# BT_PCM5102A_OPA227.net
KiCad netlist of a schematic drawn in EAGLE
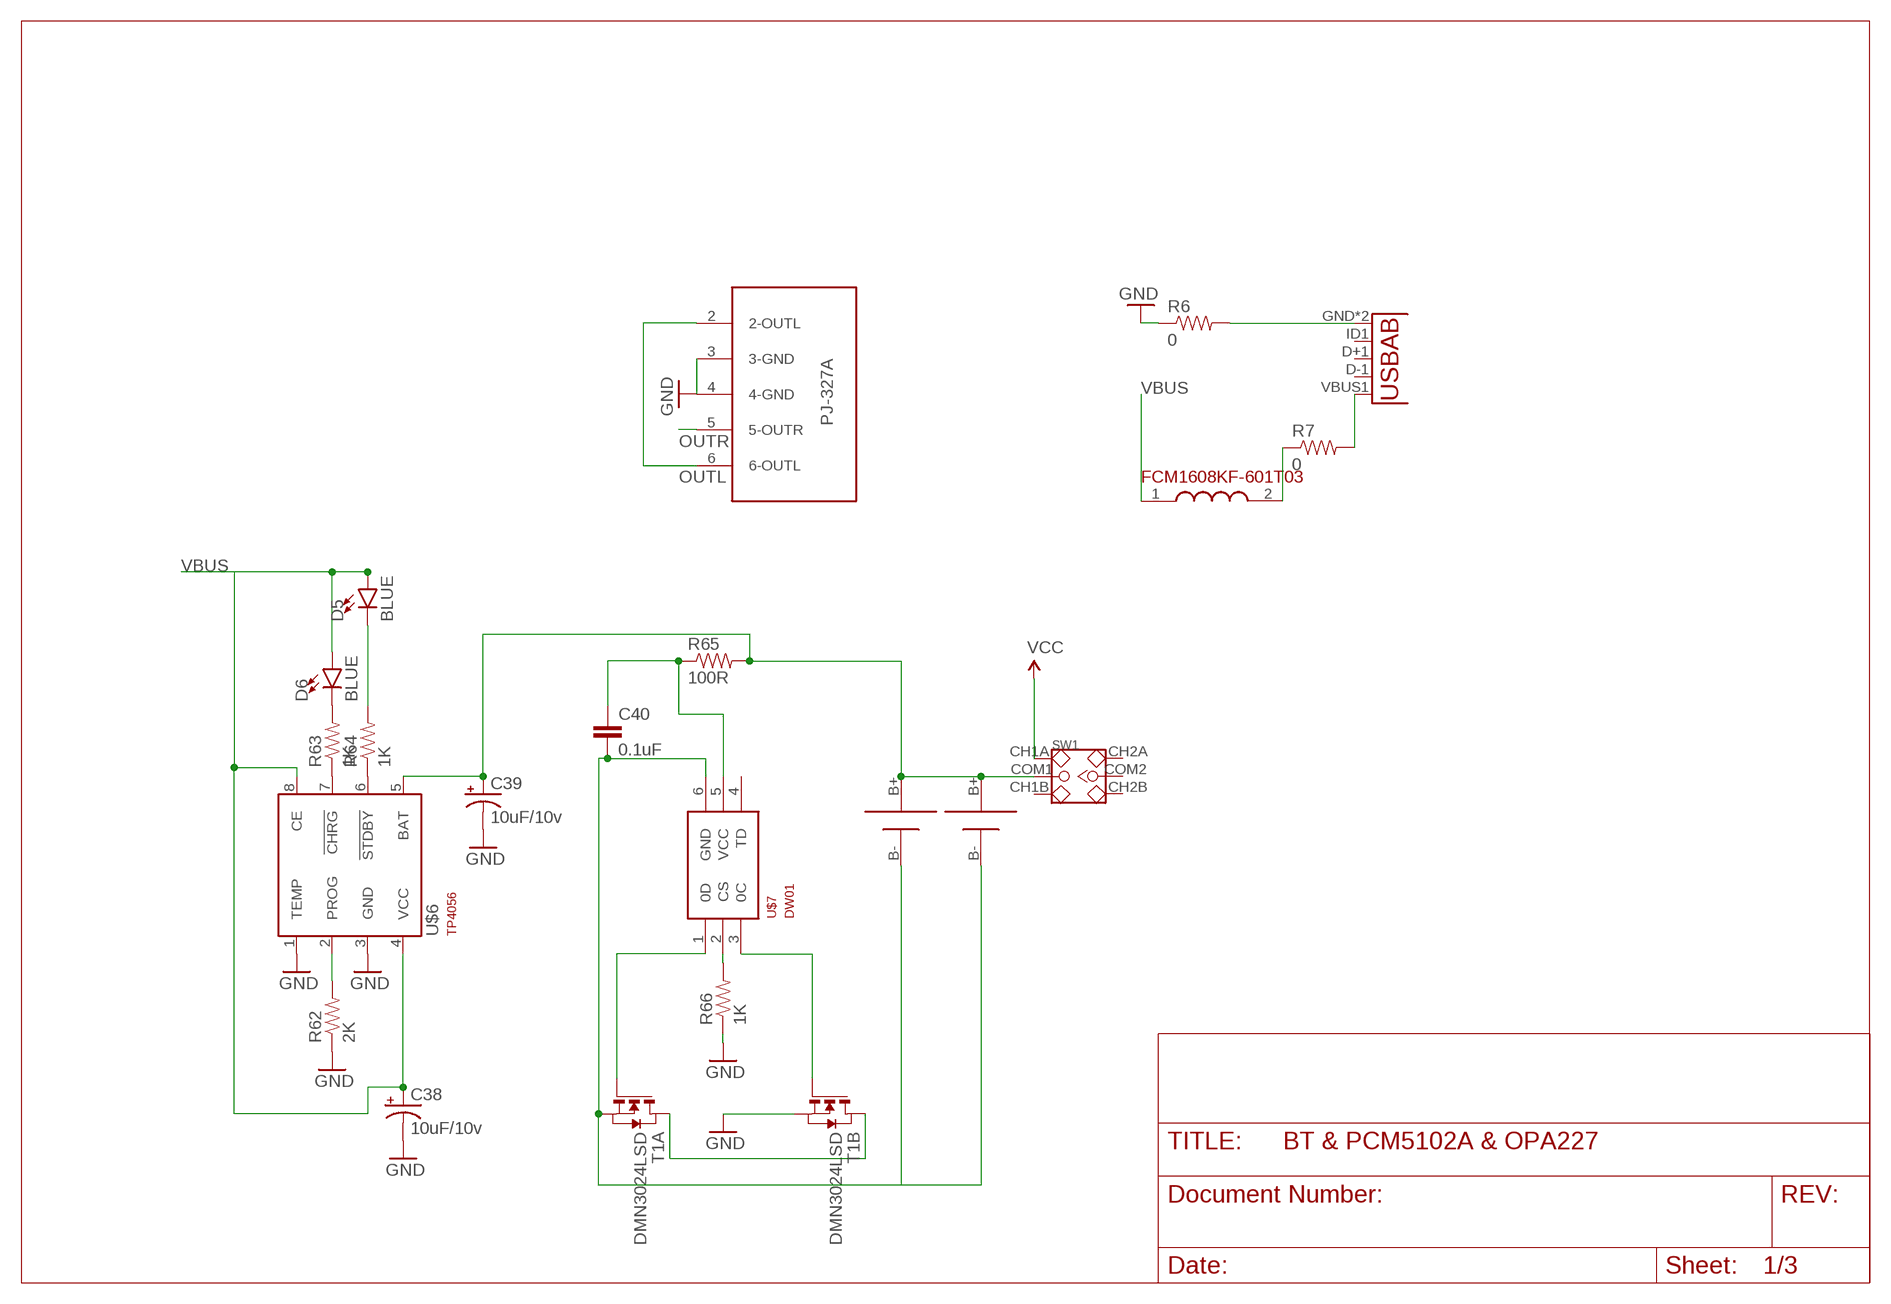
[diagram p0: schematic, sheet 1]
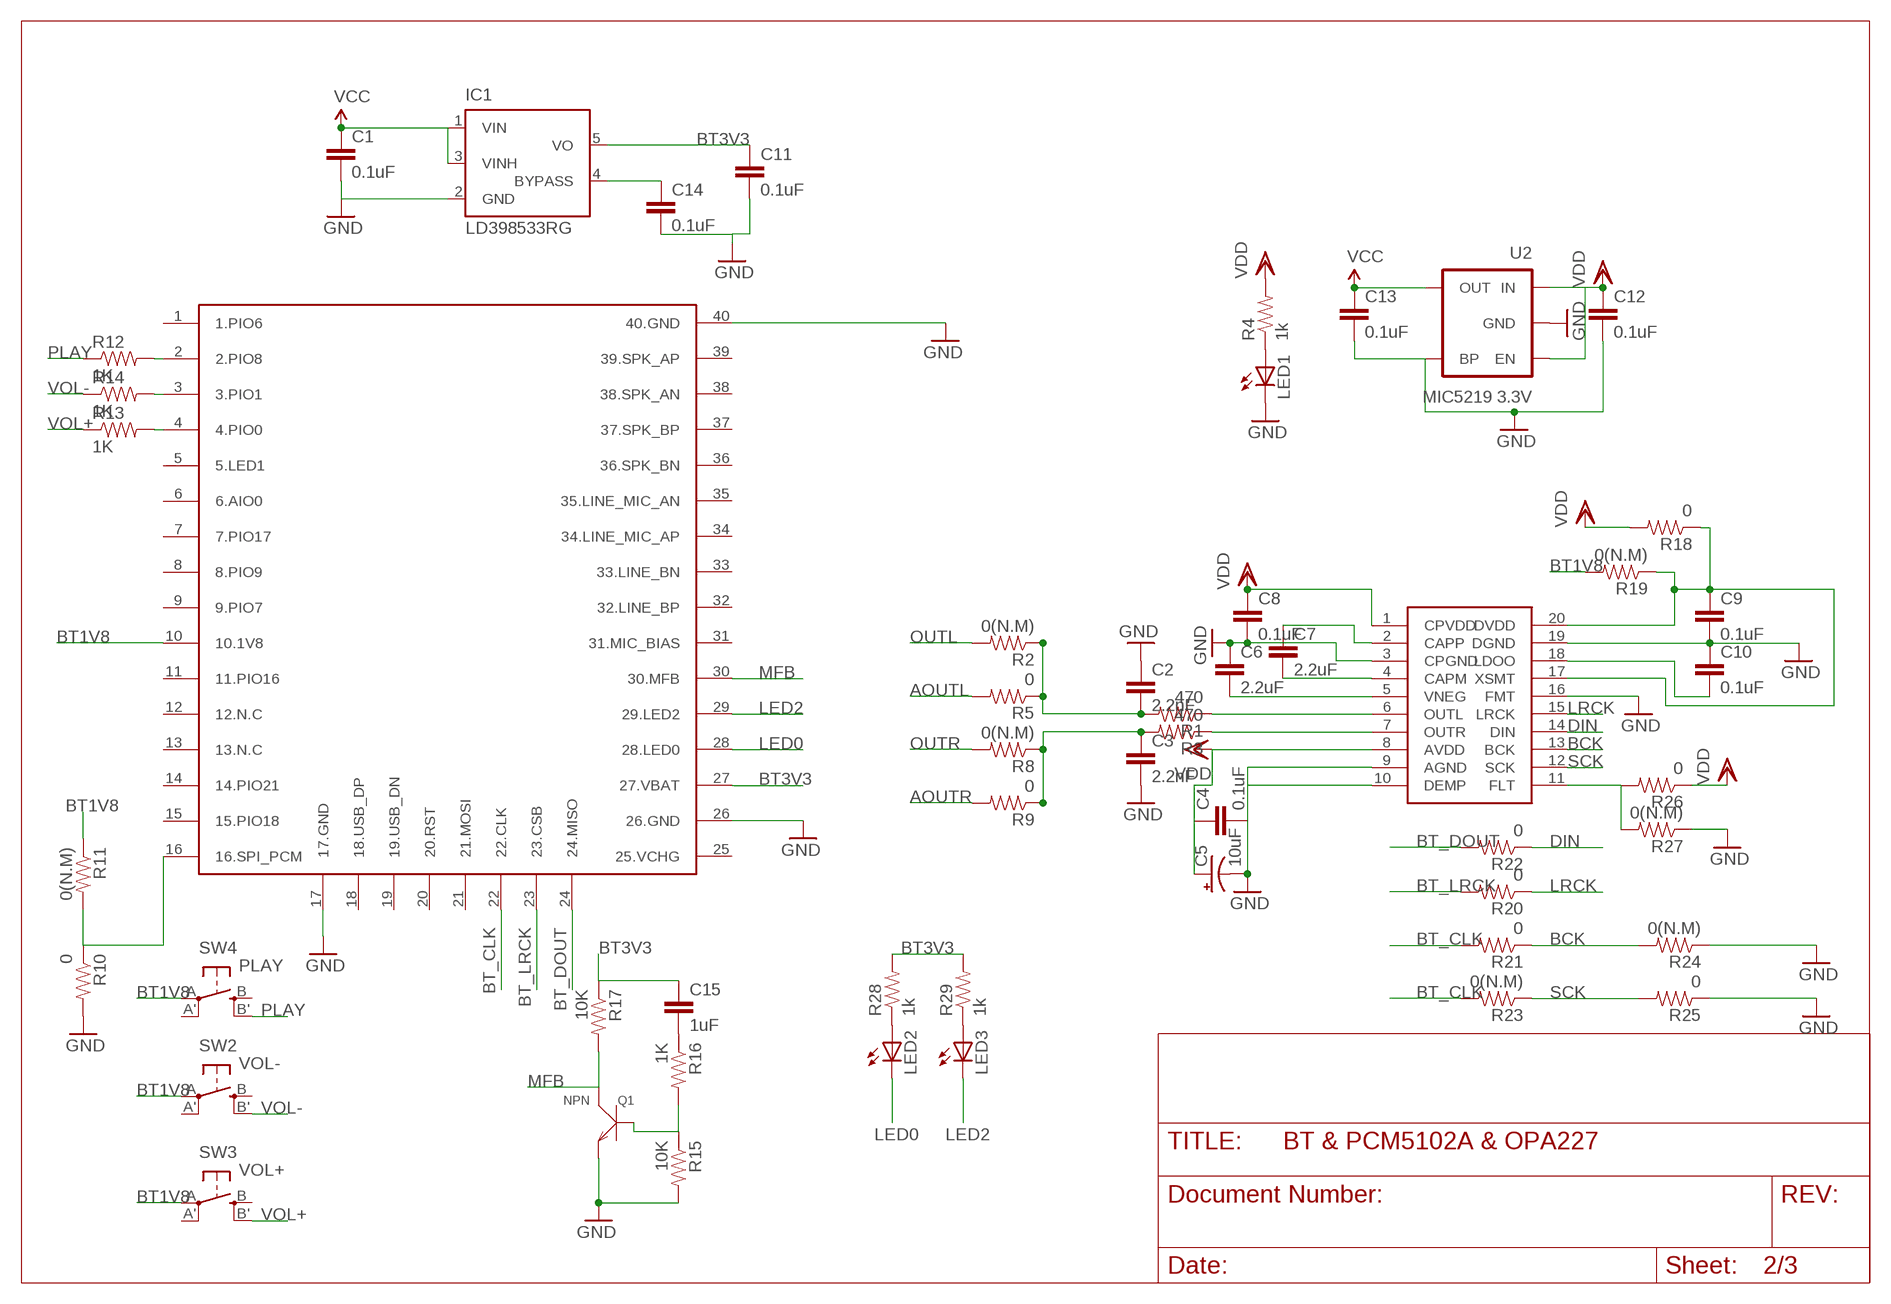
[diagram p1: schematic, sheet 2]
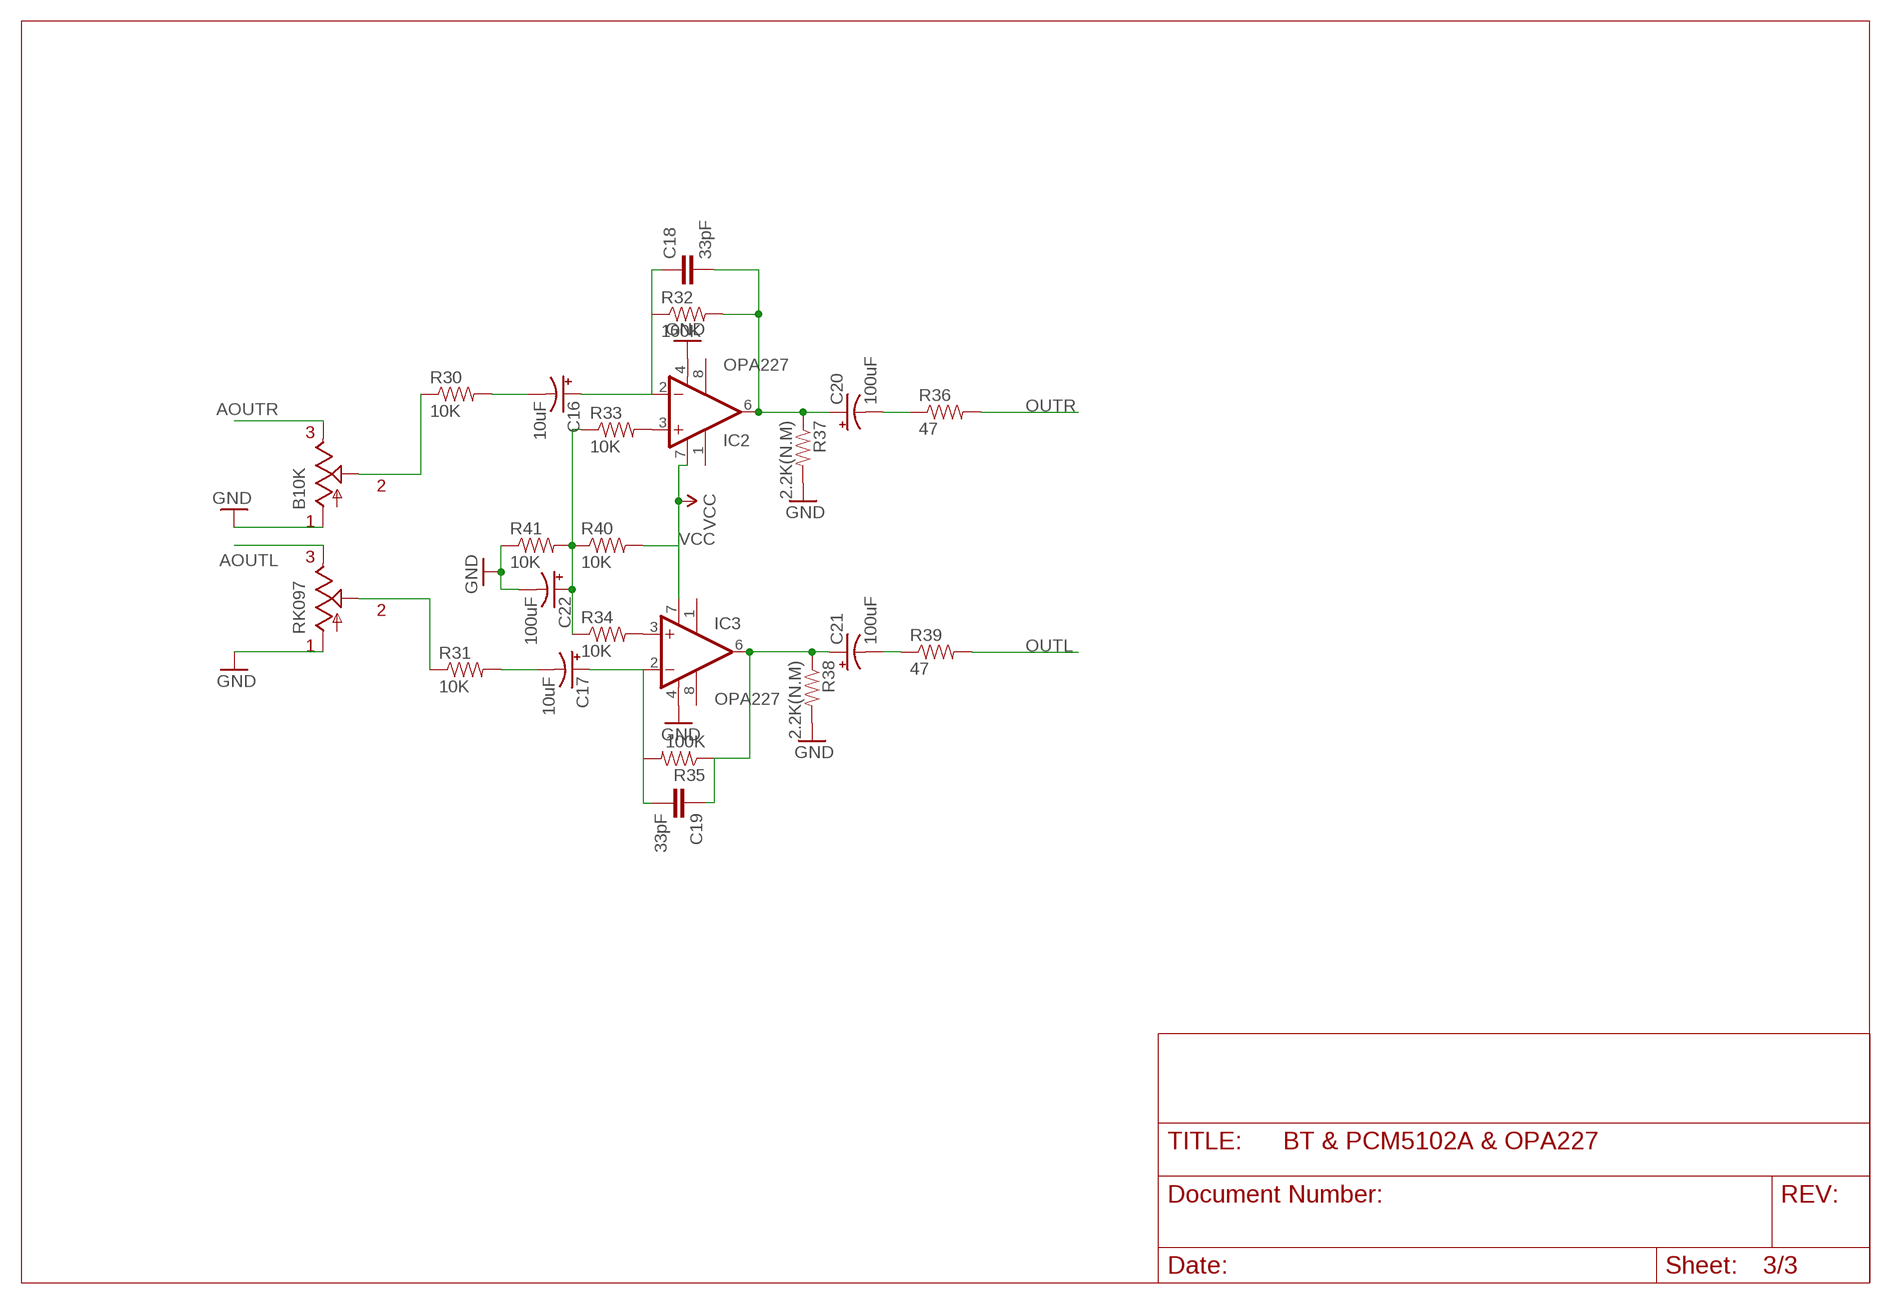
[diagram p2: schematic, sheet 3]

(export (version "E")
  (design (tool "Eeschema 10.0.6"))
  (components
    (comp (ref "C1")
      (value "0.1uF")
      (footprint "eagle-import:1206")
      (libsource (lib "eagle-import") (part "2.2UF-CERCAP-10009"))
    )
    (comp (ref "C2")
      (value "2.2nF")
      (footprint "eagle-import:C5B2.5")
      (libsource (lib "eagle-import") (part "C5/2.5"))
    )
    (comp (ref "C3")
      (value "2.2nF")
      (footprint "eagle-import:C5B2.5")
      (libsource (lib "eagle-import") (part "C5/2.5"))
    )
    (comp (ref "C4")
      (value "0.1uF")
      (footprint "eagle-import:1206")
      (libsource (lib "eagle-import") (part "2.2UF-CERCAP-10009"))
    )
    (comp (ref "C5")
      (value "10uF")
      (footprint "eagle-import:NIPPON_F80")
      (libsource (lib "eagle-import") (part "CAP_POLF80"))
    )
    (comp (ref "C6")
      (value "2.2uF")
      (footprint "eagle-import:1206")
      (libsource (lib "eagle-import") (part "2.2UF-CERCAP-10009"))
    )
    (comp (ref "C7")
      (value "2.2uF")
      (footprint "eagle-import:1206")
      (libsource (lib "eagle-import") (part "2.2UF-CERCAP-10009"))
    )
    (comp (ref "C8")
      (value "0.1uF")
      (footprint "eagle-import:1206")
      (libsource (lib "eagle-import") (part "2.2UF-CERCAP-10009"))
    )
    (comp (ref "C9")
      (value "0.1uF")
      (footprint "eagle-import:1206")
      (libsource (lib "eagle-import") (part "2.2UF-CERCAP-10009"))
    )
    (comp (ref "C10")
      (value "0.1uF")
      (footprint "eagle-import:1206")
      (libsource (lib "eagle-import") (part "2.2UF-CERCAP-10009"))
    )
    (comp (ref "C11")
      (value "0.1uF")
      (footprint "eagle-import:1206")
      (libsource (lib "eagle-import") (part "2.2UF-CERCAP-10009"))
    )
    (comp (ref "C12")
      (value "0.1uF")
      (footprint "eagle-import:1206")
      (libsource (lib "eagle-import") (part "2.2UF-CERCAP-10009"))
    )
    (comp (ref "C13")
      (value "0.1uF")
      (footprint "eagle-import:1206")
      (libsource (lib "eagle-import") (part "2.2UF-CERCAP-10009"))
    )
    (comp (ref "C14")
      (value "0.1uF")
      (footprint "eagle-import:1206")
      (libsource (lib "eagle-import") (part "2.2UF-CERCAP-10009"))
    )
    (comp (ref "C15")
      (value "1uF")
      (footprint "eagle-import:C5B2.5")
      (libsource (lib "eagle-import") (part "C5/2.5"))
    )
    (comp (ref "IC1")
      (value "LD398533RG")
      (footprint "eagle-import:TSOT23-5L")
      (libsource (lib "eagle-import") (part "LD3985G33R"))
    )
    (comp (ref "LED1")
      (value "LEDCHIP-LED0805")
      (footprint "eagle-import:CHIP-LED0805")
      (libsource (lib "eagle-import") (part "LEDCHIP-LED0805"))
    )
    (comp (ref "LED2")
      (value "LEDCHIP-LED0805")
      (footprint "eagle-import:CHIP-LED0805")
      (libsource (lib "eagle-import") (part "LEDCHIP-LED0805"))
    )
    (comp (ref "LED3")
      (value "LEDCHIP-LED0805")
      (footprint "eagle-import:CHIP-LED0805")
      (libsource (lib "eagle-import") (part "LEDCHIP-LED0805"))
    )
    (comp (ref "Q1")
      (value "NPN")
      (footprint "eagle-import:SOT-23")
      (libsource (lib "eagle-import") (part "TRANSISTOR-NPN"))
    )
    (comp (ref "R1")
      (value "470")
      (footprint "eagle-import:1206")
      (libsource (lib "eagle-import") (part "RESISTOR1206"))
    )
    (comp (ref "R2")
      (value "0(N.M)")
      (footprint "eagle-import:1206")
      (libsource (lib "eagle-import") (part "RESISTOR1206"))
    )
    (comp (ref "R3")
      (value "470")
      (footprint "eagle-import:1206")
      (libsource (lib "eagle-import") (part "RESISTOR1206"))
    )
    (comp (ref "R4")
      (value "1k")
      (footprint "eagle-import:1206")
      (libsource (lib "eagle-import") (part "RESISTOR1206"))
    )
    (comp (ref "R5")
      (value "0")
      (footprint "eagle-import:1206")
      (libsource (lib "eagle-import") (part "RESISTOR1206"))
    )
    (comp (ref "R8")
      (value "0(N.M)")
      (footprint "eagle-import:1206")
      (libsource (lib "eagle-import") (part "RESISTOR1206"))
    )
    (comp (ref "R9")
      (value "0")
      (footprint "eagle-import:1206")
      (libsource (lib "eagle-import") (part "RESISTOR1206"))
    )
    (comp (ref "R10")
      (value "0")
      (footprint "eagle-import:1206")
      (libsource (lib "eagle-import") (part "RESISTOR1206"))
    )
    (comp (ref "R11")
      (value "0(N.M)")
      (footprint "eagle-import:1206")
      (libsource (lib "eagle-import") (part "RESISTOR1206"))
    )
    (comp (ref "R12")
      (value "1K")
      (footprint "eagle-import:1206")
      (libsource (lib "eagle-import") (part "RESISTOR1206"))
    )
    (comp (ref "R13")
      (value "1K")
      (footprint "eagle-import:1206")
      (libsource (lib "eagle-import") (part "RESISTOR1206"))
    )
    (comp (ref "R14")
      (value "1K")
      (footprint "eagle-import:1206")
      (libsource (lib "eagle-import") (part "RESISTOR1206"))
    )
    (comp (ref "R15")
      (value "10K")
      (footprint "eagle-import:1206")
      (libsource (lib "eagle-import") (part "RESISTOR1206"))
    )
    (comp (ref "R16")
      (value "1K")
      (footprint "eagle-import:1206")
      (libsource (lib "eagle-import") (part "RESISTOR1206"))
    )
    (comp (ref "R17")
      (value "10K")
      (footprint "eagle-import:1206")
      (libsource (lib "eagle-import") (part "RESISTOR1206"))
    )
    (comp (ref "R18")
      (value "0")
      (footprint "eagle-import:1206")
      (libsource (lib "eagle-import") (part "RESISTOR1206"))
    )
    (comp (ref "R19")
      (value "0(N.M)")
      (footprint "eagle-import:1206")
      (libsource (lib "eagle-import") (part "RESISTOR1206"))
    )
    (comp (ref "R20")
      (value "0")
      (footprint "eagle-import:1206")
      (libsource (lib "eagle-import") (part "RESISTOR1206"))
    )
    (comp (ref "R21")
      (value "0")
      (footprint "eagle-import:1206")
      (libsource (lib "eagle-import") (part "RESISTOR1206"))
    )
    (comp (ref "R22")
      (value "0")
      (footprint "eagle-import:1206")
      (libsource (lib "eagle-import") (part "RESISTOR1206"))
    )
    (comp (ref "R23")
      (value "0(N.M)")
      (footprint "eagle-import:1206")
      (libsource (lib "eagle-import") (part "RESISTOR1206"))
    )
    (comp (ref "R24")
      (value "0(N.M)")
      (footprint "eagle-import:1206")
      (libsource (lib "eagle-import") (part "RESISTOR1206"))
    )
    (comp (ref "R25")
      (value "0")
      (footprint "eagle-import:1206")
      (libsource (lib "eagle-import") (part "RESISTOR1206"))
    )
    (comp (ref "R26")
      (value "0")
      (footprint "eagle-import:1206")
      (libsource (lib "eagle-import") (part "RESISTOR1206"))
    )
    (comp (ref "R27")
      (value "0(N.M)")
      (footprint "eagle-import:1206")
      (libsource (lib "eagle-import") (part "RESISTOR1206"))
    )
    (comp (ref "R28")
      (value "1k")
      (footprint "eagle-import:1206")
      (libsource (lib "eagle-import") (part "RESISTOR1206"))
    )
    (comp (ref "R29")
      (value "1k")
      (footprint "eagle-import:1206")
      (libsource (lib "eagle-import") (part "RESISTOR1206"))
    )
    (comp (ref "SW2")
      (value "VOL-")
      (footprint "eagle-import:EVQ-Q2")
      (libsource (lib "eagle-import") (part "SPST_TACT-EVQQ2"))
    )
    (comp (ref "SW3")
      (value "VOL+")
      (footprint "eagle-import:EVQ-Q2")
      (libsource (lib "eagle-import") (part "SPST_TACT-EVQQ2"))
    )
    (comp (ref "SW4")
      (value "PLAY")
      (footprint "eagle-import:EVQ-Q2")
      (libsource (lib "eagle-import") (part "SPST_TACT-EVQQ2"))
    )
    (comp (ref "U$1")
      (value "PCM5102")
      (footprint "eagle-import:TSSOP20")
      (libsource (lib "eagle-import") (part "PCM5102"))
    )
    (comp (ref "U$3")
      (value "BTM625")
      (footprint "eagle-import:BTM625")
      (libsource (lib "eagle-import") (part "BTM625"))
    )
    (comp (ref "U2")
      (value "MIC5219 3.3V")
      (footprint "eagle-import:SOT23-5")
      (libsource (lib "eagle-import") (part "V_REG_MIC52193.3V"))
    )
    (comp (ref "C16")
      (value "10uF")
      (footprint "eagle-import:CPOL-RADIAL-2.5MM-5MM-KIT")
      (libsource (lib "eagle-import") (part "10UF-POLAR-RADIAL-2.5MM-KIT-25V-20%"))
    )
    (comp (ref "C17")
      (value "10uF")
      (footprint "eagle-import:CPOL-RADIAL-2.5MM-5MM-KIT")
      (libsource (lib "eagle-import") (part "10UF-POLAR-RADIAL-2.5MM-KIT-25V-20%"))
    )
    (comp (ref "C18")
      (value "33pF")
      (footprint "eagle-import:0603")
      (libsource (lib "eagle-import") (part "22PF-0603-50V-5%"))
    )
    (comp (ref "C19")
      (value "33pF")
      (footprint "eagle-import:0603")
      (libsource (lib "eagle-import") (part "22PF-0603-50V-5%"))
    )
    (comp (ref "C20")
      (value "100uF")
      (footprint "eagle-import:CPOL-RADIAL-2.5MM-5MM-KIT")
      (libsource (lib "eagle-import") (part "10UF-POLAR-RADIAL-2.5MM-KIT-25V-20%"))
    )
    (comp (ref "C21")
      (value "100uF")
      (footprint "eagle-import:CPOL-RADIAL-2.5MM-5MM-KIT")
      (libsource (lib "eagle-import") (part "10UF-POLAR-RADIAL-2.5MM-KIT-25V-20%"))
    )
    (comp (ref "C22")
      (value "100uF")
      (footprint "eagle-import:CPOL-RADIAL-2.5MM-5MM-KIT")
      (libsource (lib "eagle-import") (part "10UF-POLAR-RADIAL-2.5MM-KIT-25V-20%"))
    )
    (comp (ref "IC2")
      (value "OPA227")
      (footprint "eagle-import:SO08")
      (libsource (lib "eagle-import") (part "OPA22D"))
    )
    (comp (ref "IC3")
      (value "OPA227")
      (footprint "eagle-import:SO08")
      (libsource (lib "eagle-import") (part "OPA22D"))
    )
    (comp (ref "R30")
      (value "10K")
      (footprint "eagle-import:1206")
      (libsource (lib "eagle-import") (part "RESISTOR1206"))
    )
    (comp (ref "R31")
      (value "10K")
      (footprint "eagle-import:1206")
      (libsource (lib "eagle-import") (part "RESISTOR1206"))
    )
    (comp (ref "R32")
      (value "100K")
      (footprint "eagle-import:1206")
      (libsource (lib "eagle-import") (part "RESISTOR1206"))
    )
    (comp (ref "R33")
      (value "10K")
      (footprint "eagle-import:1206")
      (libsource (lib "eagle-import") (part "RESISTOR1206"))
    )
    (comp (ref "R34")
      (value "10K")
      (footprint "eagle-import:1206")
      (libsource (lib "eagle-import") (part "RESISTOR1206"))
    )
    (comp (ref "R35")
      (value "100K")
      (footprint "eagle-import:1206")
      (libsource (lib "eagle-import") (part "RESISTOR1206"))
    )
    (comp (ref "R36")
      (value "47")
      (footprint "eagle-import:1206")
      (libsource (lib "eagle-import") (part "RESISTOR1206"))
    )
    (comp (ref "R37")
      (value "2.2K(N.M)")
      (footprint "eagle-import:1206")
      (libsource (lib "eagle-import") (part "RESISTOR1206"))
    )
    (comp (ref "R38")
      (value "2.2K(N.M)")
      (footprint "eagle-import:1206")
      (libsource (lib "eagle-import") (part "RESISTOR1206"))
    )
    (comp (ref "R39")
      (value "47")
      (footprint "eagle-import:1206")
      (libsource (lib "eagle-import") (part "RESISTOR1206"))
    )
    (comp (ref "R40")
      (value "10K")
      (footprint "eagle-import:1206")
      (libsource (lib "eagle-import") (part "RESISTOR1206"))
    )
    (comp (ref "R41")
      (value "10K")
      (footprint "eagle-import:1206")
      (libsource (lib "eagle-import") (part "RESISTOR1206"))
    )
    (comp (ref "RK097")
      (value "B10K")
      (footprint "eagle-import:RK097-DUAL-ELEMENT")
      (libsource (lib "eagle-import") (part "RK097-DUAL-ELEMENT"))
    )
    (comp (ref "C38")
      (value "10uF/10v")
      (footprint "eagle-import:EIA3216-KIT")
      (libsource (lib "eagle-import") (part "CAP_POL1206-KIT"))
    )
    (comp (ref "C39")
      (value "10uF/10v")
      (footprint "eagle-import:EIA3216-KIT")
      (libsource (lib "eagle-import") (part "CAP_POL1206-KIT"))
    )
    (comp (ref "C40")
      (value "0.1uF")
      (footprint "eagle-import:0603-CAP")
      (libsource (lib "eagle-import") (part "0.1UF-100V-10%(0603)"))
    )
    (comp (ref "D5")
      (value "BLUE")
      (footprint "eagle-import:LED-0603")
      (libsource (lib "eagle-import") (part "LED-BLUE0603"))
    )
    (comp (ref "D6")
      (value "BLUE")
      (footprint "eagle-import:LED-0603")
      (libsource (lib "eagle-import") (part "LED-BLUE0603"))
    )
    (comp (ref "R6")
      (value "0")
      (footprint "eagle-import:0805")
      (libsource (lib "eagle-import") (part "RESISTOR0805-RES"))
    )
    (comp (ref "R7")
      (value "0")
      (footprint "eagle-import:0805")
      (libsource (lib "eagle-import") (part "RESISTOR0805-RES"))
    )
    (comp (ref "R62")
      (value "2K")
      (footprint "eagle-import:0603-RES")
      (libsource (lib "eagle-import") (part "1KOHM1/10W1%(0603)"))
    )
    (comp (ref "R63")
      (value "1K")
      (footprint "eagle-import:0603-RES")
      (libsource (lib "eagle-import") (part "1KOHM1/10W1%(0603)"))
    )
    (comp (ref "R64")
      (value "1K")
      (footprint "eagle-import:0603-RES")
      (libsource (lib "eagle-import") (part "1KOHM1/10W1%(0603)"))
    )
    (comp (ref "R65")
      (value "100R")
      (footprint "eagle-import:0603-RES")
      (libsource (lib "eagle-import") (part "1KOHM1/10W1%(0603)"))
    )
    (comp (ref "R66")
      (value "1K")
      (footprint "eagle-import:0603-RES")
      (libsource (lib "eagle-import") (part "1KOHM1/10W1%(0603)"))
    )
    (comp (ref "SW1")
      (value "SMD-TOGGLE-SWITCH-2CH(2X3P-7X3.5MM)")
      (footprint "eagle-import:SW6-2.54-SMD-7.0X3.5X1.5MM")
      (libsource (lib "eagle-import") (part "SMD-TOGGLE-SWITCH-2CH(2X3P-7X3.5MM)"))
    )
    (comp (ref "T1")
      (value "DMN3024LSD")
      (footprint "eagle-import:TSSOP-8")
      (libsource (lib "eagle-import") (part "DMN3024LSD"))
    )
    (comp (ref "U$2")
      (value "PJ-327A")
      (footprint "eagle-import:PJ-327A")
      (libsource (lib "eagle-import") (part "PJ-327A"))
    )
    (comp (ref "U$4")
      (value "FCM1608KF-601T03")
      (footprint "eagle-import:FCM1608KF-601T03")
      (libsource (lib "eagle-import") (part "FCM1608KF-601T03"))
    )
    (comp (ref "U$5")
      (value "18650SMD")
      (footprint "eagle-import:18650SMD")
      (libsource (lib "eagle-import") (part "18650SMD"))
    )
    (comp (ref "U$6")
      (value "TP4056")
      (footprint "eagle-import:SOT23-8")
      (libsource (lib "eagle-import") (part "TP4056"))
    )
    (comp (ref "U$7")
      (value "DW01")
      (footprint "eagle-import:SOT23-6")
      (libsource (lib "eagle-import") (part "DW01"))
    )
    (comp (ref "U$8")
      (value "18650SMD")
      (footprint "eagle-import:18650SMD")
      (libsource (lib "eagle-import") (part "18650SMD"))
    )
    (comp (ref "U1")
      (value "USB\"\"")
      (footprint "eagle-import:USB-MICRO-SMD")
      (libsource (lib "eagle-import") (part "USB{dblquote}{dblquote}"))
    )
  )
  (nets
    (net (code "1") (name "AOUTL") (class "Default")
      (node (ref "R5") (pin "2") (pinfunction "2_2") (pintype "passive"))
      (node (ref "RK097") (pin "P$6") (pinfunction "E1_P$6") (pintype "passive"))
    )
    (net (code "2") (name "AOUTR") (class "Default")
      (node (ref "R9") (pin "2") (pinfunction "2_2") (pintype "passive"))
      (node (ref "RK097") (pin "P$1") (pinfunction "E_P$1") (pintype "passive"))
    )
    (net (code "3") (name "BCK") (class "Default")
      (node (ref "R21") (pin "1") (pinfunction "1_1") (pintype "passive"))
      (node (ref "R24") (pin "2") (pinfunction "2_2") (pintype "passive"))
      (node (ref "U$1") (pin "13") (pinfunction "BCK_13") (pintype "bidirectional"))
    )
    (net (code "4") (name "BT1V8") (class "Default")
      (node (ref "R11") (pin "1") (pinfunction "1_1") (pintype "passive"))
      (node (ref "R19") (pin "2") (pinfunction "2_2") (pintype "passive"))
      (node (ref "SW2") (pin "A") (pinfunction "P_A") (pintype "passive"))
      (node (ref "SW3") (pin "A") (pinfunction "P_A") (pintype "passive"))
      (node (ref "SW4") (pin "A") (pinfunction "P_A") (pintype "passive"))
      (node (ref "U$3") (pin "10") (pinfunction "10.1V8_10") (pintype "bidirectional"))
    )
    (net (code "5") (name "BT3V3") (class "Default")
      (node (ref "C11") (pin "1") (pinfunction "1_1") (pintype "passive"))
      (node (ref "C15") (pin "1") (pinfunction "1_1") (pintype "passive"))
      (node (ref "IC1") (pin "5") (pinfunction "VO_5") (pintype "output"))
      (node (ref "R17") (pin "1") (pinfunction "1_1") (pintype "passive"))
      (node (ref "R28") (pin "2") (pinfunction "2_2") (pintype "passive"))
      (node (ref "R29") (pin "2") (pinfunction "2_2") (pintype "passive"))
      (node (ref "U$3") (pin "27") (pinfunction "27.VBAT_27") (pintype "bidirectional"))
    )
    (net (code "6") (name "BT_CLK") (class "Default")
      (node (ref "R21") (pin "2") (pinfunction "2_2") (pintype "passive"))
      (node (ref "R23") (pin "2") (pinfunction "2_2") (pintype "passive"))
      (node (ref "U$3") (pin "22") (pinfunction "22.CLK_22") (pintype "bidirectional"))
    )
    (net (code "7") (name "BT_DOUT") (class "Default")
      (node (ref "R22") (pin "2") (pinfunction "2_2") (pintype "passive"))
      (node (ref "U$3") (pin "24") (pinfunction "24.MISO_24") (pintype "bidirectional"))
    )
    (net (code "8") (name "BT_LRCK") (class "Default")
      (node (ref "R20") (pin "2") (pinfunction "2_2") (pintype "passive"))
      (node (ref "U$3") (pin "23") (pinfunction "23.CSB_23") (pintype "bidirectional"))
    )
    (net (code "9") (name "DIN") (class "Default")
      (node (ref "R22") (pin "1") (pinfunction "1_1") (pintype "passive"))
      (node (ref "U$1") (pin "14") (pinfunction "DIN_14") (pintype "bidirectional"))
    )
    (net (code "10") (name "GND") (class "Default")
      (node (ref "C1") (pin "2") (pinfunction "2_2") (pintype "passive"))
      (node (ref "C10") (pin "1") (pinfunction "1_1") (pintype "passive"))
      (node (ref "C11") (pin "2") (pinfunction "2_2") (pintype "passive"))
      (node (ref "C12") (pin "2") (pinfunction "2_2") (pintype "passive"))
      (node (ref "C13") (pin "2") (pinfunction "2_2") (pintype "passive"))
      (node (ref "C14") (pin "2") (pinfunction "2_2") (pintype "passive"))
      (node (ref "C2") (pin "1") (pinfunction "1_1") (pintype "passive"))
      (node (ref "C22") (pin "2") (pinfunction "-_2") (pintype "passive"))
      (node (ref "C3") (pin "2") (pinfunction "2_2") (pintype "passive"))
      (node (ref "C38") (pin "C") (pinfunction "-_C") (pintype "passive"))
      (node (ref "C39") (pin "C") (pinfunction "-_C") (pintype "passive"))
      (node (ref "C4") (pin "2") (pinfunction "2_2") (pintype "passive"))
      (node (ref "C5") (pin "-") (pinfunction "-_-") (pintype "passive"))
      (node (ref "C6") (pin "1") (pinfunction "1_1") (pintype "passive"))
      (node (ref "C8") (pin "2") (pinfunction "2_2") (pintype "passive"))
      (node (ref "C9") (pin "2") (pinfunction "2_2") (pintype "passive"))
      (node (ref "IC1") (pin "2") (pinfunction "GND_2") (pintype "power_in"))
      (node (ref "IC2") (pin "4") (pinfunction "V-_4") (pintype "power_in"))
      (node (ref "IC3") (pin "4") (pinfunction "V-_4") (pintype "power_in"))
      (node (ref "LED1") (pin "C") (pinfunction "C_C") (pintype "passive"))
      (node (ref "Q1") (pin "2") (pinfunction "E_2") (pintype "passive"))
      (node (ref "R10") (pin "2") (pinfunction "2_2") (pintype "passive"))
      (node (ref "R15") (pin "2") (pinfunction "2_2") (pintype "passive"))
      (node (ref "R24") (pin "1") (pinfunction "1_1") (pintype "passive"))
      (node (ref "R25") (pin "1") (pinfunction "1_1") (pintype "passive"))
      (node (ref "R27") (pin "1") (pinfunction "1_1") (pintype "passive"))
      (node (ref "R37") (pin "2") (pinfunction "2_2") (pintype "passive"))
      (node (ref "R38") (pin "2") (pinfunction "2_2") (pintype "passive"))
      (node (ref "R41") (pin "1") (pinfunction "1_1") (pintype "passive"))
      (node (ref "R6") (pin "1") (pinfunction "1_1") (pintype "passive"))
      (node (ref "R62") (pin "1") (pinfunction "1_1") (pintype "passive"))
      (node (ref "R66") (pin "1") (pinfunction "1_1") (pintype "passive"))
      (node (ref "RK097") (pin "P$3") (pinfunction "A_P$3") (pintype "passive"))
      (node (ref "RK097") (pin "P$4") (pinfunction "A1_P$4") (pintype "passive"))
      (node (ref "T1") (pin "6") (pinfunction "S_6") (pintype "passive"))
      (node (ref "T1") (pin "7") (pinfunction "S_7") (pintype "passive"))
      (node (ref "U$1") (pin "10") (pinfunction "DEMP_10") (pintype "bidirectional"))
      (node (ref "U$1") (pin "16") (pinfunction "FMT_16") (pintype "bidirectional"))
      (node (ref "U$1") (pin "19") (pinfunction "DGND_19") (pintype "bidirectional"))
      (node (ref "U$1") (pin "3") (pinfunction "CPGND_3") (pintype "bidirectional"))
      (node (ref "U$1") (pin "9") (pinfunction "AGND_9") (pintype "bidirectional"))
      (node (ref "U$2") (pin "3") (pinfunction "3-GND_3") (pintype "bidirectional"))
      (node (ref "U$2") (pin "4") (pinfunction "4-GND_4") (pintype "bidirectional"))
      (node (ref "U$3") (pin "17") (pinfunction "17.GND_17") (pintype "bidirectional"))
      (node (ref "U$3") (pin "26") (pinfunction "26.GND_26") (pintype "bidirectional"))
      (node (ref "U$3") (pin "40") (pinfunction "40.GND_40") (pintype "bidirectional"))
      (node (ref "U$6") (pin "1") (pinfunction "TEMP_1") (pintype "bidirectional"))
      (node (ref "U$6") (pin "3") (pinfunction "GND_3") (pintype "bidirectional"))
      (node (ref "U2") (pin "2") (pinfunction "GND_2") (pintype "input"))
      (node (ref "U2") (pin "4") (pinfunction "BP_4") (pintype "input"))
    )
    (net (code "11") (name "LED0") (class "Default")
      (node (ref "LED2") (pin "C") (pinfunction "C_C") (pintype "passive"))
      (node (ref "U$3") (pin "28") (pinfunction "28.LED0_28") (pintype "bidirectional"))
    )
    (net (code "12") (name "LED2") (class "Default")
      (node (ref "LED3") (pin "C") (pinfunction "C_C") (pintype "passive"))
      (node (ref "U$3") (pin "29") (pinfunction "29.LED2_29") (pintype "bidirectional"))
    )
    (net (code "13") (name "LRCK") (class "Default")
      (node (ref "R20") (pin "1") (pinfunction "1_1") (pintype "passive"))
      (node (ref "U$1") (pin "15") (pinfunction "LRCK_15") (pintype "bidirectional"))
    )
    (net (code "14") (name "MFB") (class "Default")
      (node (ref "Q1") (pin "3") (pinfunction "C_3") (pintype "passive"))
      (node (ref "R17") (pin "2") (pinfunction "2_2") (pintype "passive"))
      (node (ref "U$3") (pin "30") (pinfunction "30.MFB_30") (pintype "bidirectional"))
    )
    (net (code "15") (name "Net-(C15-Pad2)") (class "Default")
      (node (ref "C15") (pin "2") (pinfunction "2_2") (pintype "passive"))
      (node (ref "R16") (pin "1") (pinfunction "1_1") (pintype "passive"))
    )
    (net (code "16") (name "Net-(C16-+)") (class "Default")
      (node (ref "C16") (pin "1") (pinfunction "+_1") (pintype "passive"))
      (node (ref "C18") (pin "1") (pinfunction "1_1") (pintype "passive"))
      (node (ref "IC2") (pin "2") (pinfunction "-IN_2") (pintype "input"))
      (node (ref "R32") (pin "1") (pinfunction "1_1") (pintype "passive"))
    )
    (net (code "17") (name "Net-(C16--)") (class "Default")
      (node (ref "C16") (pin "2") (pinfunction "-_2") (pintype "passive"))
      (node (ref "R30") (pin "2") (pinfunction "2_2") (pintype "passive"))
    )
    (net (code "18") (name "Net-(C17-+)") (class "Default")
      (node (ref "C17") (pin "1") (pinfunction "+_1") (pintype "passive"))
      (node (ref "C19") (pin "2") (pinfunction "2_2") (pintype "passive"))
      (node (ref "IC3") (pin "2") (pinfunction "-IN_2") (pintype "input"))
      (node (ref "R35") (pin "2") (pinfunction "2_2") (pintype "passive"))
    )
    (net (code "19") (name "Net-(C17--)") (class "Default")
      (node (ref "C17") (pin "2") (pinfunction "-_2") (pintype "passive"))
      (node (ref "R31") (pin "2") (pinfunction "2_2") (pintype "passive"))
    )
    (net (code "20") (name "Net-(C20-+)") (class "Default")
      (node (ref "C18") (pin "2") (pinfunction "2_2") (pintype "passive"))
      (node (ref "C20") (pin "1") (pinfunction "+_1") (pintype "passive"))
      (node (ref "IC2") (pin "6") (pinfunction "OUT_6") (pintype "output"))
      (node (ref "R32") (pin "2") (pinfunction "2_2") (pintype "passive"))
      (node (ref "R37") (pin "1") (pinfunction "1_1") (pintype "passive"))
    )
    (net (code "21") (name "Net-(C20--)") (class "Default")
      (node (ref "C20") (pin "2") (pinfunction "-_2") (pintype "passive"))
      (node (ref "R36") (pin "1") (pinfunction "1_1") (pintype "passive"))
    )
    (net (code "22") (name "Net-(C21-+)") (class "Default")
      (node (ref "C19") (pin "1") (pinfunction "1_1") (pintype "passive"))
      (node (ref "C21") (pin "1") (pinfunction "+_1") (pintype "passive"))
      (node (ref "IC3") (pin "6") (pinfunction "OUT_6") (pintype "output"))
      (node (ref "R35") (pin "1") (pinfunction "1_1") (pintype "passive"))
      (node (ref "R38") (pin "1") (pinfunction "1_1") (pintype "passive"))
    )
    (net (code "23") (name "Net-(C21--)") (class "Default")
      (node (ref "C21") (pin "2") (pinfunction "-_2") (pintype "passive"))
      (node (ref "R39") (pin "1") (pinfunction "1_1") (pintype "passive"))
    )
    (net (code "24") (name "Net-(C22-+)") (class "Default")
      (node (ref "C22") (pin "1") (pinfunction "+_1") (pintype "passive"))
      (node (ref "R33") (pin "1") (pinfunction "1_1") (pintype "passive"))
      (node (ref "R34") (pin "1") (pinfunction "1_1") (pintype "passive"))
      (node (ref "R40") (pin "1") (pinfunction "1_1") (pintype "passive"))
      (node (ref "R41") (pin "2") (pinfunction "2_2") (pintype "passive"))
    )
    (net (code "25") (name "Net-(C39-+)") (class "Default")
      (node (ref "C39") (pin "A") (pinfunction "+_A") (pintype "passive"))
      (node (ref "R65") (pin "2") (pinfunction "2_2") (pintype "passive"))
      (node (ref "SW1") (pin "COM1") (pinfunction "COM1_COM1") (pintype "bidirectional"))
      (node (ref "U$5") (pin "B+") (pinfunction "B+_B+") (pintype "bidirectional"))
      (node (ref "U$6") (pin "5") (pinfunction "BAT_5") (pintype "bidirectional"))
      (node (ref "U$8") (pin "B+") (pinfunction "B+_B+") (pintype "bidirectional"))
    )
    (net (code "26") (name "Net-(D5-PadC)") (class "Default")
      (node (ref "D5") (pin "C") (pinfunction "C_C") (pintype "passive"))
      (node (ref "R64") (pin "2") (pinfunction "2_2") (pintype "passive"))
    )
    (net (code "27") (name "Net-(D6-PadC)") (class "Default")
      (node (ref "D6") (pin "C") (pinfunction "C_C") (pintype "passive"))
      (node (ref "R63") (pin "2") (pinfunction "2_2") (pintype "passive"))
    )
    (net (code "28") (name "Net-(IC1-BYPASS)") (class "Default")
      (node (ref "C14") (pin "1") (pinfunction "1_1") (pintype "passive"))
      (node (ref "IC1") (pin "4") (pinfunction "BYPASS_4") (pintype "passive"))
    )
    (net (code "29") (name "Net-(IC2-+IN)") (class "Default")
      (node (ref "IC2") (pin "3") (pinfunction "+IN_3") (pintype "input"))
      (node (ref "R33") (pin "2") (pinfunction "2_2") (pintype "passive"))
    )
    (net (code "30") (name "Net-(IC3-+IN)") (class "Default")
      (node (ref "IC3") (pin "3") (pinfunction "+IN_3") (pintype "input"))
      (node (ref "R34") (pin "2") (pinfunction "2_2") (pintype "passive"))
    )
    (net (code "31") (name "Net-(LED1-PadA)") (class "Default")
      (node (ref "LED1") (pin "A") (pinfunction "A_A") (pintype "passive"))
      (node (ref "R4") (pin "1") (pinfunction "1_1") (pintype "passive"))
    )
    (net (code "32") (name "Net-(LED2-PadA)") (class "Default")
      (node (ref "LED2") (pin "A") (pinfunction "A_A") (pintype "passive"))
      (node (ref "R28") (pin "1") (pinfunction "1_1") (pintype "passive"))
    )
    (net (code "33") (name "Net-(LED3-PadA)") (class "Default")
      (node (ref "LED3") (pin "A") (pinfunction "A_A") (pintype "passive"))
      (node (ref "R29") (pin "1") (pinfunction "1_1") (pintype "passive"))
    )
    (net (code "34") (name "Net-(Q1-B)") (class "Default")
      (node (ref "Q1") (pin "1") (pinfunction "B_1") (pintype "passive"))
      (node (ref "R15") (pin "1") (pinfunction "1_1") (pintype "passive"))
      (node (ref "R16") (pin "2") (pinfunction "2_2") (pintype "passive"))
    )
    (net (code "35") (name "Net-(R6-Pad2)") (class "Default")
      (node (ref "R6") (pin "2") (pinfunction "2_2") (pintype "passive"))
      (node (ref "U1") (pin "GND") (pinfunction "GND_GND") (pintype "bidirectional"))
      (node (ref "U1") (pin "GND1") (pinfunction "GND_GND1") (pintype "bidirectional"))
    )
    (net (code "36") (name "Net-(RK097-S)") (class "Default")
      (node (ref "R30") (pin "1") (pinfunction "1_1") (pintype "passive"))
      (node (ref "RK097") (pin "P$2") (pinfunction "S_P$2") (pintype "passive"))
    )
    (net (code "37") (name "Net-(RK097-S1)") (class "Default")
      (node (ref "R31") (pin "1") (pinfunction "1_1") (pintype "passive"))
      (node (ref "RK097") (pin "P$5") (pinfunction "S1_P$5") (pintype "passive"))
    )
    (net (code "38") (name "Net-(T1A-D)") (class "Default")
      (node (ref "T1") (pin "1") (pinfunction "D_1") (pintype "passive"))
      (node (ref "T1") (pin "8") (pinfunction "D_8") (pintype "passive"))
    )
    (net (code "39") (name "Net-(T1A-G)") (class "Default")
      (node (ref "T1") (pin "4") (pinfunction "G_4") (pintype "passive"))
      (node (ref "U$7") (pin "1") (pinfunction "0D_1") (pintype "bidirectional"))
    )
    (net (code "40") (name "Net-(T1B-G)") (class "Default")
      (node (ref "T1") (pin "5") (pinfunction "G_5") (pintype "passive"))
      (node (ref "U$7") (pin "3") (pinfunction "0C_3") (pintype "bidirectional"))
    )
    (net (code "41") (name "Net-(U$1-CAPM)") (class "Default")
      (node (ref "C7") (pin "2") (pinfunction "2_2") (pintype "passive"))
      (node (ref "U$1") (pin "4") (pinfunction "CAPM_4") (pintype "bidirectional"))
    )
    (net (code "42") (name "Net-(U$1-CAPP)") (class "Default")
      (node (ref "C7") (pin "1") (pinfunction "1_1") (pintype "passive"))
      (node (ref "U$1") (pin "2") (pinfunction "CAPP_2") (pintype "bidirectional"))
    )
    (net (code "43") (name "Net-(U$1-DVDD)") (class "Default")
      (node (ref "C9") (pin "1") (pinfunction "1_1") (pintype "passive"))
      (node (ref "R18") (pin "1") (pinfunction "1_1") (pintype "passive"))
      (node (ref "R19") (pin "1") (pinfunction "1_1") (pintype "passive"))
      (node (ref "U$1") (pin "17") (pinfunction "XSMT_17") (pintype "bidirectional"))
      (node (ref "U$1") (pin "20") (pinfunction "DVDD_20") (pintype "bidirectional"))
    )
    (net (code "44") (name "Net-(U$1-FLT)") (class "Default")
      (node (ref "R26") (pin "2") (pinfunction "2_2") (pintype "passive"))
      (node (ref "R27") (pin "2") (pinfunction "2_2") (pintype "passive"))
      (node (ref "U$1") (pin "11") (pinfunction "FLT_11") (pintype "bidirectional"))
    )
    (net (code "45") (name "Net-(U$1-LDOO)") (class "Default")
      (node (ref "C10") (pin "2") (pinfunction "2_2") (pintype "passive"))
      (node (ref "U$1") (pin "18") (pinfunction "LDOO_18") (pintype "bidirectional"))
    )
    (net (code "46") (name "Net-(U$1-OUTL)") (class "Default")
      (node (ref "R1") (pin "1") (pinfunction "1_1") (pintype "passive"))
      (node (ref "U$1") (pin "6") (pinfunction "OUTL_6") (pintype "bidirectional"))
    )
    (net (code "47") (name "Net-(U$1-OUTR)") (class "Default")
      (node (ref "R3") (pin "1") (pinfunction "1_1") (pintype "passive"))
      (node (ref "U$1") (pin "7") (pinfunction "OUTR_7") (pintype "bidirectional"))
    )
    (net (code "48") (name "Net-(U$1-VNEG)") (class "Default")
      (node (ref "C6") (pin "2") (pinfunction "2_2") (pintype "passive"))
      (node (ref "U$1") (pin "5") (pinfunction "VNEG_5") (pintype "bidirectional"))
    )
    (net (code "49") (name "Net-(U$3-2.PIO8)") (class "Default")
      (node (ref "R12") (pin "2") (pinfunction "2_2") (pintype "passive"))
      (node (ref "U$3") (pin "2") (pinfunction "2.PIO8_2") (pintype "bidirectional"))
    )
    (net (code "50") (name "Net-(U$3-3.PIO1)") (class "Default")
      (node (ref "R14") (pin "2") (pinfunction "2_2") (pintype "passive"))
      (node (ref "U$3") (pin "3") (pinfunction "3.PIO1_3") (pintype "bidirectional"))
    )
    (net (code "51") (name "Net-(U$3-4.PIO0)") (class "Default")
      (node (ref "R13") (pin "2") (pinfunction "2_2") (pintype "passive"))
      (node (ref "U$3") (pin "4") (pinfunction "4.PIO0_4") (pintype "bidirectional"))
    )
    (net (code "52") (name "Net-(U$3-16.SPI_PCM)") (class "Default")
      (node (ref "R10") (pin "1") (pinfunction "1_1") (pintype "passive"))
      (node (ref "R11") (pin "2") (pinfunction "2_2") (pintype "passive"))
      (node (ref "U$3") (pin "16") (pinfunction "16.SPI_PCM_16") (pintype "bidirectional"))
    )
    (net (code "53") (name "Net-(U$4-2.OUT)") (class "Default")
      (node (ref "R7") (pin "1") (pinfunction "1_1") (pintype "passive"))
      (node (ref "U$4") (pin "2") (pinfunction "2.OUT_2") (pintype "bidirectional"))
    )
    (net (code "54") (name "Net-(U$6-PROG)") (class "Default")
      (node (ref "R62") (pin "2") (pinfunction "2_2") (pintype "passive"))
      (node (ref "U$6") (pin "2") (pinfunction "PROG_2") (pintype "bidirectional"))
    )
    (net (code "55") (name "Net-(U$6-~{CHRG})") (class "Default")
      (node (ref "R63") (pin "1") (pinfunction "1_1") (pintype "passive"))
      (node (ref "U$6") (pin "7") (pinfunction "~{CHRG}_7") (pintype "bidirectional"))
    )
    (net (code "56") (name "Net-(U$6-~{STDBY})") (class "Default")
      (node (ref "R64") (pin "1") (pinfunction "1_1") (pintype "passive"))
      (node (ref "U$6") (pin "6") (pinfunction "~{STDBY}_6") (pintype "bidirectional"))
    )
    (net (code "57") (name "Net-(U$7-CS)") (class "Default")
      (node (ref "R66") (pin "2") (pinfunction "2_2") (pintype "passive"))
      (node (ref "U$7") (pin "2") (pinfunction "CS_2") (pintype "bidirectional"))
    )
    (net (code "58") (name "Net-(U$7-GND)") (class "Default")
      (node (ref "C40") (pin "2") (pinfunction "2_2") (pintype "passive"))
      (node (ref "T1") (pin "2") (pinfunction "S_2") (pintype "passive"))
      (node (ref "T1") (pin "3") (pinfunction "S_3") (pintype "passive"))
      (node (ref "U$5") (pin "B-") (pinfunction "B-_B-") (pintype "bidirectional"))
      (node (ref "U$7") (pin "6") (pinfunction "GND_6") (pintype "bidirectional"))
      (node (ref "U$8") (pin "B-") (pinfunction "B-_B-") (pintype "bidirectional"))
    )
    (net (code "59") (name "Net-(U$7-VCC)") (class "Default")
      (node (ref "C40") (pin "1") (pinfunction "1_1") (pintype "passive"))
      (node (ref "R65") (pin "1") (pinfunction "1_1") (pintype "passive"))
      (node (ref "U$7") (pin "5") (pinfunction "VCC_5") (pintype "bidirectional"))
    )
    (net (code "60") (name "Net-(U1-VBUS)") (class "Default")
      (node (ref "R7") (pin "2") (pinfunction "2_2") (pintype "passive"))
      (node (ref "U1") (pin "VBUS1") (pinfunction "VBUS_VBUS1") (pintype "bidirectional"))
    )
    (net (code "61") (name "OUTL") (class "Default")
      (node (ref "C2") (pin "2") (pinfunction "2_2") (pintype "passive"))
      (node (ref "R1") (pin "2") (pinfunction "2_2") (pintype "passive"))
      (node (ref "R2") (pin "1") (pinfunction "1_1") (pintype "passive"))
      (node (ref "R2") (pin "2") (pinfunction "2_2") (pintype "passive"))
      (node (ref "R39") (pin "2") (pinfunction "2_2") (pintype "passive"))
      (node (ref "R5") (pin "1") (pinfunction "1_1") (pintype "passive"))
      (node (ref "U$2") (pin "2") (pinfunction "2-OUTL_2") (pintype "bidirectional"))
      (node (ref "U$2") (pin "6") (pinfunction "6-OUTL_6") (pintype "bidirectional"))
    )
    (net (code "62") (name "OUTR") (class "Default")
      (node (ref "C3") (pin "1") (pinfunction "1_1") (pintype "passive"))
      (node (ref "R3") (pin "2") (pinfunction "2_2") (pintype "passive"))
      (node (ref "R36") (pin "2") (pinfunction "2_2") (pintype "passive"))
      (node (ref "R8") (pin "1") (pinfunction "1_1") (pintype "passive"))
      (node (ref "R8") (pin "2") (pinfunction "2_2") (pintype "passive"))
      (node (ref "R9") (pin "1") (pinfunction "1_1") (pintype "passive"))
      (node (ref "U$2") (pin "5") (pinfunction "5-OUTR_5") (pintype "bidirectional"))
    )
    (net (code "63") (name "PLAY") (class "Default")
      (node (ref "R12") (pin "1") (pinfunction "1_1") (pintype "passive"))
      (node (ref "SW4") (pin "B'") (pinfunction "S1_B'") (pintype "passive"))
    )
    (net (code "64") (name "SCK") (class "Default")
      (node (ref "R23") (pin "1") (pinfunction "1_1") (pintype "passive"))
      (node (ref "R25") (pin "2") (pinfunction "2_2") (pintype "passive"))
      (node (ref "U$1") (pin "12") (pinfunction "SCK_12") (pintype "bidirectional"))
    )
    (net (code "65") (name "VBUS") (class "Default")
      (node (ref "C38") (pin "A") (pinfunction "+_A") (pintype "passive"))
      (node (ref "D5") (pin "A") (pinfunction "A_A") (pintype "passive"))
      (node (ref "D6") (pin "A") (pinfunction "A_A") (pintype "passive"))
      (node (ref "U$4") (pin "1") (pinfunction "1.IN_1") (pintype "bidirectional"))
      (node (ref "U$6") (pin "4") (pinfunction "VCC_4") (pintype "bidirectional"))
      (node (ref "U$6") (pin "8") (pinfunction "CE_8") (pintype "bidirectional"))
    )
    (net (code "66") (name "VCC") (class "Default")
      (node (ref "C1") (pin "1") (pinfunction "1_1") (pintype "passive"))
      (node (ref "C13") (pin "1") (pinfunction "1_1") (pintype "passive"))
      (node (ref "IC1") (pin "1") (pinfunction "VIN_1") (pintype "input"))
      (node (ref "IC1") (pin "3") (pinfunction "VINH_3") (pintype "input"))
      (node (ref "IC2") (pin "7") (pinfunction "V+_7") (pintype "power_in"))
      (node (ref "IC3") (pin "7") (pinfunction "V+_7") (pintype "power_in"))
      (node (ref "R40") (pin "2") (pinfunction "2_2") (pintype "passive"))
      (node (ref "SW1") (pin "CH1A") (pinfunction "CH1A_CH1A") (pintype "bidirectional"))
      (node (ref "U2") (pin "5") (pinfunction "OUT_5") (pintype "passive"))
    )
    (net (code "67") (name "VDD") (class "Default")
      (node (ref "C12") (pin "1") (pinfunction "1_1") (pintype "passive"))
      (node (ref "C4") (pin "1") (pinfunction "1_1") (pintype "passive"))
      (node (ref "C5") (pin "+") (pinfunction "+_+") (pintype "passive"))
      (node (ref "C8") (pin "1") (pinfunction "1_1") (pintype "passive"))
      (node (ref "R18") (pin "2") (pinfunction "2_2") (pintype "passive"))
      (node (ref "R26") (pin "1") (pinfunction "1_1") (pintype "passive"))
      (node (ref "R4") (pin "2") (pinfunction "2_2") (pintype "passive"))
      (node (ref "U$1") (pin "1") (pinfunction "CPVDD_1") (pintype "bidirectional"))
      (node (ref "U$1") (pin "8") (pinfunction "AVDD_8") (pintype "bidirectional"))
      (node (ref "U2") (pin "1") (pinfunction "IN_1") (pintype "input"))
      (node (ref "U2") (pin "3") (pinfunction "EN_3") (pintype "input"))
    )
    (net (code "68") (name "VOL+") (class "Default")
      (node (ref "R13") (pin "1") (pinfunction "1_1") (pintype "passive"))
      (node (ref "SW3") (pin "B'") (pinfunction "S1_B'") (pintype "passive"))
    )
    (net (code "69") (name "VOL-") (class "Default")
      (node (ref "R14") (pin "1") (pinfunction "1_1") (pintype "passive"))
      (node (ref "SW2") (pin "B'") (pinfunction "S1_B'") (pintype "passive"))
    )
    (net (code "70") (name "unconnected-(IC2-OFF1-Pad1)") (class "Default")
      (node (ref "IC2") (pin "1") (pinfunction "OFF1_1") (pintype "passive"))
    )
    (net (code "71") (name "unconnected-(IC2-OFF2-Pad8)") (class "Default")
      (node (ref "IC2") (pin "8") (pinfunction "OFF2_8") (pintype "passive"))
    )
    (net (code "72") (name "unconnected-(IC3-OFF1-Pad1)") (class "Default")
      (node (ref "IC3") (pin "1") (pinfunction "OFF1_1") (pintype "passive"))
    )
    (net (code "73") (name "unconnected-(IC3-OFF2-Pad8)") (class "Default")
      (node (ref "IC3") (pin "8") (pinfunction "OFF2_8") (pintype "passive"))
    )
    (net (code "74") (name "unconnected-(SW1-PadCH1B)") (class "Default")
      (node (ref "SW1") (pin "CH1B") (pinfunction "CH1B_CH1B") (pintype "bidirectional"))
    )
    (net (code "75") (name "unconnected-(SW1-PadCH2A)") (class "Default")
      (node (ref "SW1") (pin "CH2A") (pinfunction "CH2A_CH2A") (pintype "bidirectional"))
    )
    (net (code "76") (name "unconnected-(SW1-PadCH2B)") (class "Default")
      (node (ref "SW1") (pin "CH2B") (pinfunction "CH2B_CH2B") (pintype "bidirectional"))
    )
    (net (code "77") (name "unconnected-(SW1-PadCOM2)") (class "Default")
      (node (ref "SW1") (pin "COM2") (pinfunction "COM2_COM2") (pintype "bidirectional"))
    )
    (net (code "78") (name "unconnected-(SW2-P1-PadA')") (class "Default")
      (node (ref "SW2") (pin "A'") (pinfunction "P1_A'") (pintype "passive"))
    )
    (net (code "79") (name "unconnected-(SW2-S-PadB)") (class "Default")
      (node (ref "SW2") (pin "B") (pinfunction "S_B") (pintype "passive"))
    )
    (net (code "80") (name "unconnected-(SW3-P1-PadA')") (class "Default")
      (node (ref "SW3") (pin "A'") (pinfunction "P1_A'") (pintype "passive"))
    )
    (net (code "81") (name "unconnected-(SW3-S-PadB)") (class "Default")
      (node (ref "SW3") (pin "B") (pinfunction "S_B") (pintype "passive"))
    )
    (net (code "82") (name "unconnected-(SW4-P1-PadA')") (class "Default")
      (node (ref "SW4") (pin "A'") (pinfunction "P1_A'") (pintype "passive"))
    )
    (net (code "83") (name "unconnected-(SW4-S-PadB)") (class "Default")
      (node (ref "SW4") (pin "B") (pinfunction "S_B") (pintype "passive"))
    )
    (net (code "84") (name "unconnected-(U$3-1.PIO6-Pad1)") (class "Default")
      (node (ref "U$3") (pin "1") (pinfunction "1.PIO6_1") (pintype "bidirectional"))
    )
    (net (code "85") (name "unconnected-(U$3-5.LED1-Pad5)") (class "Default")
      (node (ref "U$3") (pin "5") (pinfunction "5.LED1_5") (pintype "bidirectional"))
    )
    (net (code "86") (name "unconnected-(U$3-6.AIO0-Pad6)") (class "Default")
      (node (ref "U$3") (pin "6") (pinfunction "6.AIO0_6") (pintype "bidirectional"))
    )
    (net (code "87") (name "unconnected-(U$3-7.PIO17-Pad7)") (class "Default")
      (node (ref "U$3") (pin "7") (pinfunction "7.PIO17_7") (pintype "bidirectional"))
    )
    (net (code "88") (name "unconnected-(U$3-8.PIO9-Pad8)") (class "Default")
      (node (ref "U$3") (pin "8") (pinfunction "8.PIO9_8") (pintype "bidirectional"))
    )
    (net (code "89") (name "unconnected-(U$3-9.PIO7-Pad9)") (class "Default")
      (node (ref "U$3") (pin "9") (pinfunction "9.PIO7_9") (pintype "bidirectional"))
    )
    (net (code "90") (name "unconnected-(U$3-11.PIO16-Pad11)") (class "Default")
      (node (ref "U$3") (pin "11") (pinfunction "11.PIO16_11") (pintype "bidirectional"))
    )
    (net (code "91") (name "unconnected-(U$3-12.N.C-Pad12)") (class "Default")
      (node (ref "U$3") (pin "12") (pinfunction "12.N.C_12") (pintype "bidirectional"))
    )
    (net (code "92") (name "unconnected-(U$3-13.N.C-Pad13)") (class "Default")
      (node (ref "U$3") (pin "13") (pinfunction "13.N.C_13") (pintype "bidirectional"))
    )
    (net (code "93") (name "unconnected-(U$3-14.PIO21-Pad14)") (class "Default")
      (node (ref "U$3") (pin "14") (pinfunction "14.PIO21_14") (pintype "bidirectional"))
    )
    (net (code "94") (name "unconnected-(U$3-15.PIO18-Pad15)") (class "Default")
      (node (ref "U$3") (pin "15") (pinfunction "15.PIO18_15") (pintype "bidirectional"))
    )
    (net (code "95") (name "unconnected-(U$3-18.USB_DP-Pad18)") (class "Default")
      (node (ref "U$3") (pin "18") (pinfunction "18.USB_DP_18") (pintype "bidirectional"))
    )
    (net (code "96") (name "unconnected-(U$3-19.USB_DN-Pad19)") (class "Default")
      (node (ref "U$3") (pin "19") (pinfunction "19.USB_DN_19") (pintype "bidirectional"))
    )
    (net (code "97") (name "unconnected-(U$3-20.RST-Pad20)") (class "Default")
      (node (ref "U$3") (pin "20") (pinfunction "20.RST_20") (pintype "bidirectional"))
    )
    (net (code "98") (name "unconnected-(U$3-21.MOSI-Pad21)") (class "Default")
      (node (ref "U$3") (pin "21") (pinfunction "21.MOSI_21") (pintype "bidirectional"))
    )
    (net (code "99") (name "unconnected-(U$3-25.VCHG-Pad25)") (class "Default")
      (node (ref "U$3") (pin "25") (pinfunction "25.VCHG_25") (pintype "bidirectional"))
    )
    (net (code "100") (name "unconnected-(U$3-31.MIC_BIAS-Pad31)") (class "Default")
      (node (ref "U$3") (pin "31") (pinfunction "31.MIC_BIAS_31") (pintype "bidirectional"))
    )
    (net (code "101") (name "unconnected-(U$3-32.LINE_BP-Pad32)") (class "Default")
      (node (ref "U$3") (pin "32") (pinfunction "32.LINE_BP_32") (pintype "bidirectional"))
    )
    (net (code "102") (name "unconnected-(U$3-33.LINE_BN-Pad33)") (class "Default")
      (node (ref "U$3") (pin "33") (pinfunction "33.LINE_BN_33") (pintype "bidirectional"))
    )
    (net (code "103") (name "unconnected-(U$3-34.LINE_MIC_AP-Pad34)") (class "Default")
      (node (ref "U$3") (pin "34") (pinfunction "34.LINE_MIC_AP_34") (pintype "bidirectional"))
    )
    (net (code "104") (name "unconnected-(U$3-35.LINE_MIC_AN-Pad35)") (class "Default")
      (node (ref "U$3") (pin "35") (pinfunction "35.LINE_MIC_AN_35") (pintype "bidirectional"))
    )
    (net (code "105") (name "unconnected-(U$3-36.SPK_BN-Pad36)") (class "Default")
      (node (ref "U$3") (pin "36") (pinfunction "36.SPK_BN_36") (pintype "bidirectional"))
    )
    (net (code "106") (name "unconnected-(U$3-37.SPK_BP-Pad37)") (class "Default")
      (node (ref "U$3") (pin "37") (pinfunction "37.SPK_BP_37") (pintype "bidirectional"))
    )
    (net (code "107") (name "unconnected-(U$3-38.SPK_AN-Pad38)") (class "Default")
      (node (ref "U$3") (pin "38") (pinfunction "38.SPK_AN_38") (pintype "bidirectional"))
    )
    (net (code "108") (name "unconnected-(U$3-39.SPK_AP-Pad39)") (class "Default")
      (node (ref "U$3") (pin "39") (pinfunction "39.SPK_AP_39") (pintype "bidirectional"))
    )
    (net (code "109") (name "unconnected-(U$7-TD-Pad4)") (class "Default")
      (node (ref "U$7") (pin "4") (pinfunction "TD_4") (pintype "bidirectional"))
    )
    (net (code "110") (name "unconnected-(U1-D+-PadD+1)") (class "Default")
      (node (ref "U1") (pin "D+1") (pinfunction "D+_D+1") (pintype "bidirectional"))
    )
    (net (code "111") (name "unconnected-(U1-D--PadD-1)") (class "Default")
      (node (ref "U1") (pin "D-1") (pinfunction "D-_D-1") (pintype "bidirectional"))
    )
    (net (code "112") (name "unconnected-(U1-USBID-PadID1)") (class "Default")
      (node (ref "U1") (pin "ID1") (pinfunction "USBID_ID1") (pintype "bidirectional"))
    )
  )
)
